# schematic.net
KiCad netlist of a schematic drawn in EAGLE
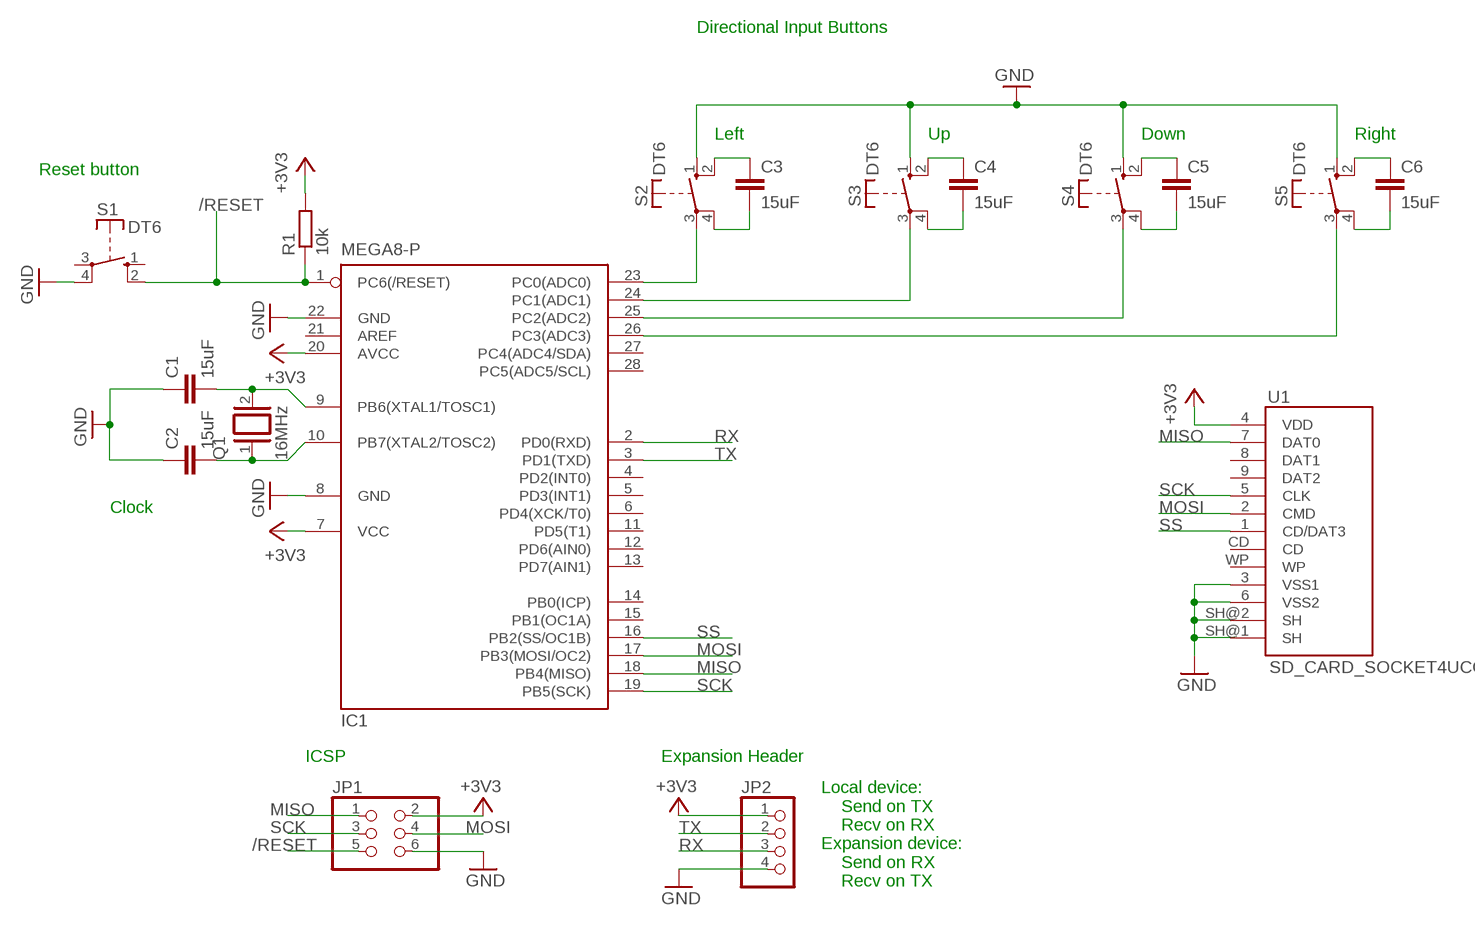
[diagram p0: schematic, sheet 1]

(export (version "E")
  (design (tool "Eeschema 10.0.6"))
  (components
    (comp (ref "C1")
      (value "15uF")
      (footprint "eagle-import:C025-024X044")
      (libsource (lib "eagle-import") (part "C-EU025-024X044"))
    )
    (comp (ref "C2")
      (value "15uF")
      (footprint "eagle-import:C025-024X044")
      (libsource (lib "eagle-import") (part "C-EU025-024X044"))
    )
    (comp (ref "C3")
      (value "15uF")
      (footprint "eagle-import:C025-024X044")
      (libsource (lib "eagle-import") (part "C-EU025-024X044"))
    )
    (comp (ref "C4")
      (value "15uF")
      (footprint "eagle-import:C025-024X044")
      (libsource (lib "eagle-import") (part "C-EU025-024X044"))
    )
    (comp (ref "C5")
      (value "15uF")
      (footprint "eagle-import:C025-024X044")
      (libsource (lib "eagle-import") (part "C-EU025-024X044"))
    )
    (comp (ref "C6")
      (value "15uF")
      (footprint "eagle-import:C025-024X044")
      (libsource (lib "eagle-import") (part "C-EU025-024X044"))
    )
    (comp (ref "IC1")
      (value "MEGA8-P")
      (footprint "eagle-import:DIL28-3")
      (libsource (lib "eagle-import") (part "MEGA8-P"))
    )
    (comp (ref "JP1")
      (value "PINHD-2X3")
      (footprint "eagle-import:2X03")
      (libsource (lib "eagle-import") (part "PINHD-2X3"))
    )
    (comp (ref "JP2")
      (value "PINHD-1X4")
      (footprint "eagle-import:1X04")
      (libsource (lib "eagle-import") (part "PINHD-1X4"))
    )
    (comp (ref "Q1")
      (value "16MHz")
      (footprint "eagle-import:Q")
      (libsource (lib "eagle-import") (part "XTAL"))
    )
    (comp (ref "R1")
      (value "10k")
      (footprint "eagle-import:0204_7")
      (libsource (lib "eagle-import") (part "R-EU_0204/7"))
    )
    (comp (ref "S1")
      (value "DT6")
      (footprint "eagle-import:DT6")
      (libsource (lib "eagle-import") (part "DT6"))
    )
    (comp (ref "S2")
      (value "DT6")
      (footprint "eagle-import:DT6")
      (libsource (lib "eagle-import") (part "DT6"))
    )
    (comp (ref "S3")
      (value "DT6")
      (footprint "eagle-import:DT6")
      (libsource (lib "eagle-import") (part "DT6"))
    )
    (comp (ref "S4")
      (value "DT6")
      (footprint "eagle-import:DT6")
      (libsource (lib "eagle-import") (part "DT6"))
    )
    (comp (ref "S5")
      (value "DT6")
      (footprint "eagle-import:DT6")
      (libsource (lib "eagle-import") (part "DT6"))
    )
    (comp (ref "U1")
      (value "SD_CARD_SOCKET4UCON")
      (footprint "eagle-import:SDCARD_4UCONN")
      (libsource (lib "eagle-import") (part "SD_CARD_SOCKET4UCON"))
    )
  )
  (nets
    (net (code "1") (name "+3V3") (class "Default")
      (node (ref "IC1") (pin "20") (pinfunction "AVCC_20") (pintype "power_in"))
      (node (ref "IC1") (pin "7") (pinfunction "VCC_7") (pintype "power_in"))
      (node (ref "JP1") (pin "2") (pinfunction "2_2") (pintype "passive"))
      (node (ref "JP2") (pin "1") (pinfunction "1_1") (pintype "passive"))
      (node (ref "R1") (pin "2") (pinfunction "2_2") (pintype "passive"))
      (node (ref "U1") (pin "4") (pinfunction "VDD_4") (pintype "power_in"))
    )
    (net (code "2") (name "/MISO") (class "Default")
      (node (ref "IC1") (pin "18") (pinfunction "PB4(MISO)_18") (pintype "bidirectional"))
      (node (ref "JP1") (pin "1") (pinfunction "1_1") (pintype "passive"))
      (node (ref "U1") (pin "7") (pinfunction "DAT0_7") (pintype "bidirectional"))
    )
    (net (code "3") (name "/MOSI") (class "Default")
      (node (ref "IC1") (pin "17") (pinfunction "PB3(MOSI/OC2)_17") (pintype "bidirectional"))
      (node (ref "JP1") (pin "4") (pinfunction "4_4") (pintype "passive"))
      (node (ref "U1") (pin "2") (pinfunction "CMD_2") (pintype "bidirectional"))
    )
    (net (code "4") (name "/RX") (class "Default")
      (node (ref "IC1") (pin "2") (pinfunction "PD0(RXD)_2") (pintype "bidirectional"))
      (node (ref "JP2") (pin "3") (pinfunction "3_3") (pintype "passive"))
    )
    (net (code "5") (name "/SCK") (class "Default")
      (node (ref "IC1") (pin "19") (pinfunction "PB5(SCK)_19") (pintype "bidirectional"))
      (node (ref "JP1") (pin "3") (pinfunction "3_3") (pintype "passive"))
      (node (ref "U1") (pin "5") (pinfunction "CLK_5") (pintype "bidirectional"))
    )
    (net (code "6") (name "/SS") (class "Default")
      (node (ref "IC1") (pin "16") (pinfunction "PB2(SS/OC1B)_16") (pintype "bidirectional"))
      (node (ref "U1") (pin "1") (pinfunction "CD/DAT3_1") (pintype "bidirectional"))
    )
    (net (code "7") (name "/TX") (class "Default")
      (node (ref "IC1") (pin "3") (pinfunction "PD1(TXD)_3") (pintype "bidirectional"))
      (node (ref "JP2") (pin "2") (pinfunction "2_2") (pintype "passive"))
    )
    (net (code "8") (name "/{slash}RESET") (class "Default")
      (node (ref "IC1") (pin "1") (pinfunction "PC6(/RESET)_1") (pintype "bidirectional"))
      (node (ref "JP1") (pin "5") (pinfunction "5_5") (pintype "passive"))
      (node (ref "R1") (pin "1") (pinfunction "1_1") (pintype "passive"))
      (node (ref "S1") (pin "2") (pinfunction "S_2") (pintype "passive"))
    )
    (net (code "9") (name "GND") (class "Default")
      (node (ref "C1") (pin "1") (pinfunction "1_1") (pintype "passive"))
      (node (ref "C2") (pin "1") (pinfunction "1_1") (pintype "passive"))
      (node (ref "IC1") (pin "22") (pinfunction "GND_22") (pintype "power_in"))
      (node (ref "IC1") (pin "8") (pinfunction "GND_8") (pintype "power_in"))
      (node (ref "JP1") (pin "6") (pinfunction "6_6") (pintype "passive"))
      (node (ref "JP2") (pin "4") (pinfunction "4_4") (pintype "passive"))
      (node (ref "S1") (pin "4") (pinfunction "P_4") (pintype "passive"))
      (node (ref "S2") (pin "1") (pinfunction "S_1") (pintype "passive"))
      (node (ref "S3") (pin "1") (pinfunction "S_1") (pintype "passive"))
      (node (ref "S4") (pin "1") (pinfunction "S_1") (pintype "passive"))
      (node (ref "S5") (pin "1") (pinfunction "S_1") (pintype "passive"))
      (node (ref "U1") (pin "3") (pinfunction "VSS1_3") (pintype "power_in"))
      (node (ref "U1") (pin "6") (pinfunction "VSS2_6") (pintype "power_in"))
      (node (ref "U1") (pin "SH@1") (pinfunction "SH_SH@1") (pintype "bidirectional"))
      (node (ref "U1") (pin "SH@2") (pinfunction "SH_SH@2") (pintype "bidirectional"))
    )
    (net (code "10") (name "Net-(C3-Pad1)") (class "Default")
      (node (ref "C3") (pin "1") (pinfunction "1_1") (pintype "passive"))
      (node (ref "S2") (pin "2") (pinfunction "S_2") (pintype "passive"))
    )
    (net (code "11") (name "Net-(C3-Pad2)") (class "Default")
      (node (ref "C3") (pin "2") (pinfunction "2_2") (pintype "passive"))
      (node (ref "S2") (pin "4") (pinfunction "P_4") (pintype "passive"))
    )
    (net (code "12") (name "Net-(C4-Pad1)") (class "Default")
      (node (ref "C4") (pin "1") (pinfunction "1_1") (pintype "passive"))
      (node (ref "S3") (pin "2") (pinfunction "S_2") (pintype "passive"))
    )
    (net (code "13") (name "Net-(C4-Pad2)") (class "Default")
      (node (ref "C4") (pin "2") (pinfunction "2_2") (pintype "passive"))
      (node (ref "S3") (pin "4") (pinfunction "P_4") (pintype "passive"))
    )
    (net (code "14") (name "Net-(C5-Pad1)") (class "Default")
      (node (ref "C5") (pin "1") (pinfunction "1_1") (pintype "passive"))
      (node (ref "S4") (pin "2") (pinfunction "S_2") (pintype "passive"))
    )
    (net (code "15") (name "Net-(C5-Pad2)") (class "Default")
      (node (ref "C5") (pin "2") (pinfunction "2_2") (pintype "passive"))
      (node (ref "S4") (pin "4") (pinfunction "P_4") (pintype "passive"))
    )
    (net (code "16") (name "Net-(C6-Pad1)") (class "Default")
      (node (ref "C6") (pin "1") (pinfunction "1_1") (pintype "passive"))
      (node (ref "S5") (pin "2") (pinfunction "S_2") (pintype "passive"))
    )
    (net (code "17") (name "Net-(C6-Pad2)") (class "Default")
      (node (ref "C6") (pin "2") (pinfunction "2_2") (pintype "passive"))
      (node (ref "S5") (pin "4") (pinfunction "P_4") (pintype "passive"))
    )
    (net (code "18") (name "Net-(IC1-PB6(XTAL1{slash}TOSC1))") (class "Default")
      (node (ref "C1") (pin "2") (pinfunction "2_2") (pintype "passive"))
      (node (ref "IC1") (pin "9") (pinfunction "PB6(XTAL1/TOSC1)_9") (pintype "bidirectional"))
      (node (ref "Q1") (pin "2") (pinfunction "2_2") (pintype "passive"))
    )
    (net (code "19") (name "Net-(IC1-PB7(XTAL2{slash}TOSC2))") (class "Default")
      (node (ref "C2") (pin "2") (pinfunction "2_2") (pintype "passive"))
      (node (ref "IC1") (pin "10") (pinfunction "PB7(XTAL2/TOSC2)_10") (pintype "bidirectional"))
      (node (ref "Q1") (pin "1") (pinfunction "1_1") (pintype "passive"))
    )
    (net (code "20") (name "Net-(IC1-PC0(ADC0))") (class "Default")
      (node (ref "IC1") (pin "23") (pinfunction "PC0(ADC0)_23") (pintype "bidirectional"))
      (node (ref "S2") (pin "3") (pinfunction "P_3") (pintype "passive"))
    )
    (net (code "21") (name "Net-(IC1-PC1(ADC1))") (class "Default")
      (node (ref "IC1") (pin "24") (pinfunction "PC1(ADC1)_24") (pintype "bidirectional"))
      (node (ref "S3") (pin "3") (pinfunction "P_3") (pintype "passive"))
    )
    (net (code "22") (name "Net-(IC1-PC2(ADC2))") (class "Default")
      (node (ref "IC1") (pin "25") (pinfunction "PC2(ADC2)_25") (pintype "bidirectional"))
      (node (ref "S4") (pin "3") (pinfunction "P_3") (pintype "passive"))
    )
    (net (code "23") (name "Net-(IC1-PC3(ADC3))") (class "Default")
      (node (ref "IC1") (pin "26") (pinfunction "PC3(ADC3)_26") (pintype "bidirectional"))
      (node (ref "S5") (pin "3") (pinfunction "P_3") (pintype "passive"))
    )
    (net (code "24") (name "unconnected-(IC1-AREF-Pad21)") (class "Default")
      (node (ref "IC1") (pin "21") (pinfunction "AREF_21") (pintype "passive"))
    )
    (net (code "25") (name "unconnected-(IC1-PB0(ICP)-Pad14)") (class "Default")
      (node (ref "IC1") (pin "14") (pinfunction "PB0(ICP)_14") (pintype "bidirectional"))
    )
    (net (code "26") (name "unconnected-(IC1-PB1(OC1A)-Pad15)") (class "Default")
      (node (ref "IC1") (pin "15") (pinfunction "PB1(OC1A)_15") (pintype "bidirectional"))
    )
    (net (code "27") (name "unconnected-(IC1-PC4(ADC4{slash}SDA)-Pad27)") (class "Default")
      (node (ref "IC1") (pin "27") (pinfunction "PC4(ADC4/SDA)_27") (pintype "bidirectional"))
    )
    (net (code "28") (name "unconnected-(IC1-PC5(ADC5{slash}SCL)-Pad28)") (class "Default")
      (node (ref "IC1") (pin "28") (pinfunction "PC5(ADC5/SCL)_28") (pintype "bidirectional"))
    )
    (net (code "29") (name "unconnected-(IC1-PD2(INT0)-Pad4)") (class "Default")
      (node (ref "IC1") (pin "4") (pinfunction "PD2(INT0)_4") (pintype "bidirectional"))
    )
    (net (code "30") (name "unconnected-(IC1-PD3(INT1)-Pad5)") (class "Default")
      (node (ref "IC1") (pin "5") (pinfunction "PD3(INT1)_5") (pintype "bidirectional"))
    )
    (net (code "31") (name "unconnected-(IC1-PD4(XCK{slash}T0)-Pad6)") (class "Default")
      (node (ref "IC1") (pin "6") (pinfunction "PD4(XCK/T0)_6") (pintype "bidirectional"))
    )
    (net (code "32") (name "unconnected-(IC1-PD5(T1)-Pad11)") (class "Default")
      (node (ref "IC1") (pin "11") (pinfunction "PD5(T1)_11") (pintype "bidirectional"))
    )
    (net (code "33") (name "unconnected-(IC1-PD6(AIN0)-Pad12)") (class "Default")
      (node (ref "IC1") (pin "12") (pinfunction "PD6(AIN0)_12") (pintype "bidirectional"))
    )
    (net (code "34") (name "unconnected-(IC1-PD7(AIN1)-Pad13)") (class "Default")
      (node (ref "IC1") (pin "13") (pinfunction "PD7(AIN1)_13") (pintype "bidirectional"))
    )
    (net (code "35") (name "unconnected-(S1-P-Pad3)") (class "Default")
      (node (ref "S1") (pin "3") (pinfunction "P_3") (pintype "passive"))
    )
    (net (code "36") (name "unconnected-(S1-S-Pad1)") (class "Default")
      (node (ref "S1") (pin "1") (pinfunction "S_1") (pintype "passive"))
    )
    (net (code "37") (name "unconnected-(U1-DAT1-Pad8)") (class "Default")
      (node (ref "U1") (pin "8") (pinfunction "DAT1_8") (pintype "bidirectional"))
    )
    (net (code "38") (name "unconnected-(U1-DAT2-Pad9)") (class "Default")
      (node (ref "U1") (pin "9") (pinfunction "DAT2_9") (pintype "bidirectional"))
    )
    (net (code "39") (name "unconnected-(U1-PadCD)") (class "Default")
      (node (ref "U1") (pin "CD") (pinfunction "CD_CD") (pintype "bidirectional"))
    )
    (net (code "40") (name "unconnected-(U1-PadWP)") (class "Default")
      (node (ref "U1") (pin "WP") (pinfunction "WP_WP") (pintype "bidirectional"))
    )
  )
)
